# AnalogInputModule2_r1_1.net
KiCad netlist of a schematic drawn in EAGLE
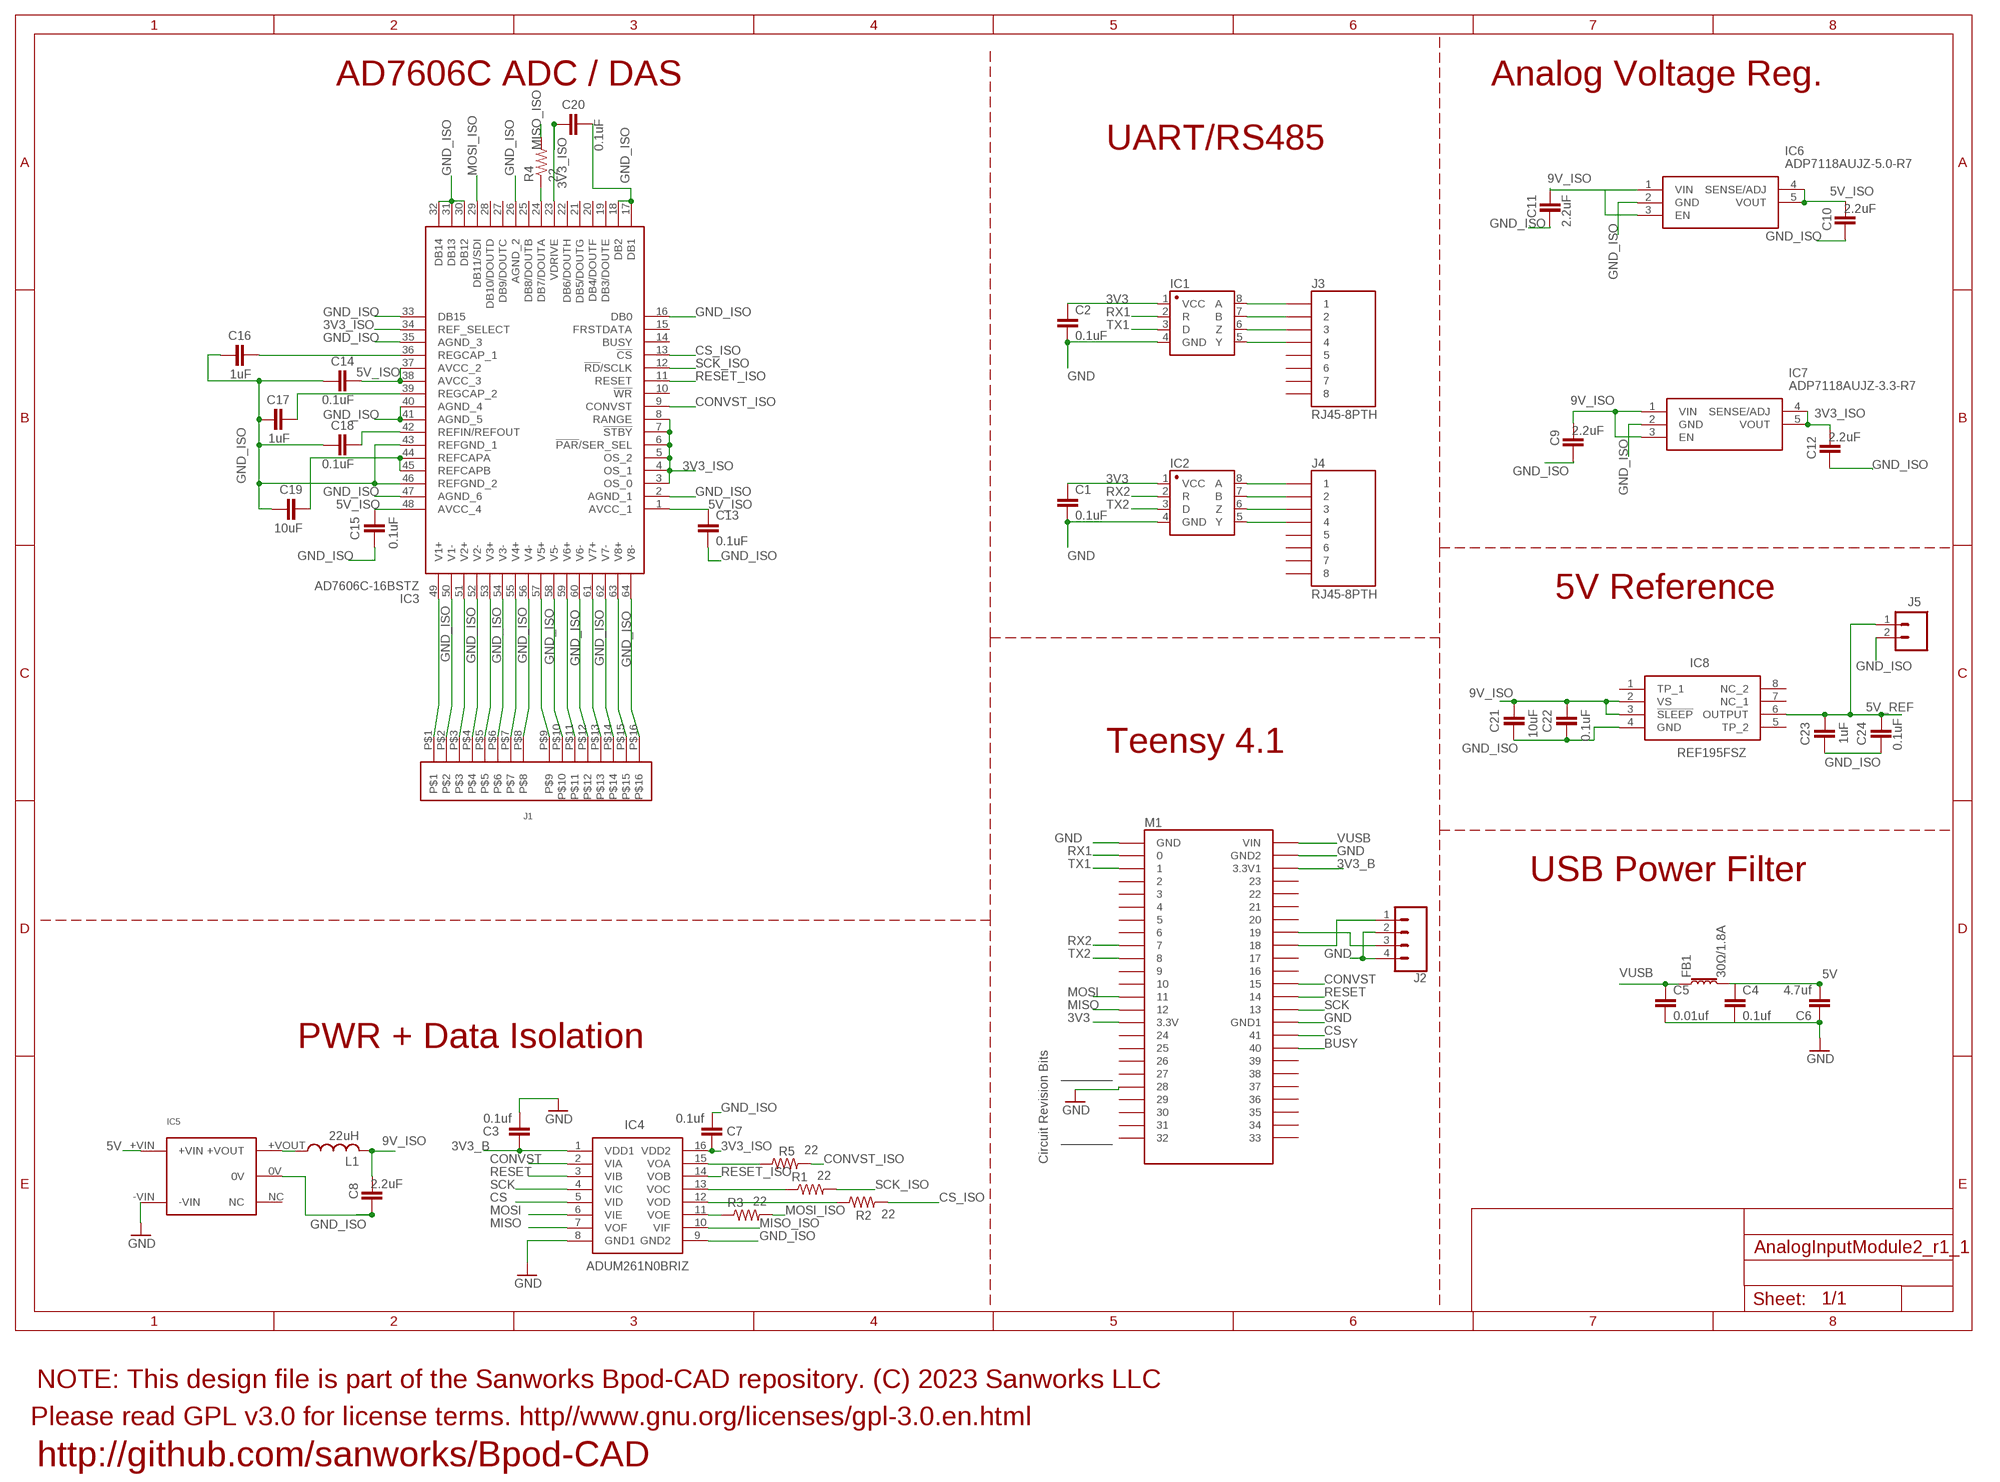
[diagram p0: schematic, sheet 1]

(export (version "E")
  (design (tool "Eeschema 10.0.6"))
  (components
    (comp (ref "C1")
      (value "0.1uF")
      (footprint "eagle-import:0805")
      (libsource (lib "eagle-import") (part "1.0UF-0805-25V-10%"))
    )
    (comp (ref "C2")
      (value "0.1uF")
      (footprint "eagle-import:0805")
      (libsource (lib "eagle-import") (part "1.0UF-0805-25V-10%"))
    )
    (comp (ref "C3")
      (value "0.1uf")
      (footprint "eagle-import:0805")
      (libsource (lib "eagle-import") (part "1.0UF-0805-25V-10%"))
    )
    (comp (ref "C4")
      (value "0.1uf")
      (footprint "eagle-import:0805")
      (libsource (lib "eagle-import") (part "10UF-0805-10V-10%"))
    )
    (comp (ref "C5")
      (value "0.01uf")
      (footprint "eagle-import:0805")
      (libsource (lib "eagle-import") (part "10UF-0805-10V-10%"))
    )
    (comp (ref "C6")
      (value "4.7uf")
      (footprint "eagle-import:1206@2")
      (libsource (lib "eagle-import") (part "CAP1206"))
    )
    (comp (ref "C7")
      (value "0.1uf")
      (footprint "eagle-import:0805")
      (libsource (lib "eagle-import") (part "1.0UF-0805-25V-10%"))
    )
    (comp (ref "C8")
      (value "2.2uF")
      (footprint "eagle-import:0805")
      (libsource (lib "eagle-import") (part "1.0UF-0805-25V-(+80/-20%)"))
    )
    (comp (ref "C9")
      (value "2.2uF")
      (footprint "eagle-import:0805")
      (libsource (lib "eagle-import") (part "1.0UF-0805-25V-(+80/-20%)"))
    )
    (comp (ref "C10")
      (value "2.2uF")
      (footprint "eagle-import:0805")
      (libsource (lib "eagle-import") (part "1.0UF-0805-25V-(+80/-20%)"))
    )
    (comp (ref "C11")
      (value "2.2uF")
      (footprint "eagle-import:0805")
      (libsource (lib "eagle-import") (part "1.0UF-0805-25V-(+80/-20%)"))
    )
    (comp (ref "C12")
      (value "2.2uF")
      (footprint "eagle-import:0805")
      (libsource (lib "eagle-import") (part "1.0UF-0805-25V-(+80/-20%)"))
    )
    (comp (ref "C13")
      (value "0.1uF")
      (footprint "eagle-import:0805")
      (libsource (lib "eagle-import") (part "1.0UF-0805-25V-10%"))
    )
    (comp (ref "C14")
      (value "0.1uF")
      (footprint "eagle-import:0805")
      (libsource (lib "eagle-import") (part "1.0UF-0805-25V-10%"))
    )
    (comp (ref "C15")
      (value "0.1uF")
      (footprint "eagle-import:0805")
      (libsource (lib "eagle-import") (part "1.0UF-0805-25V-10%"))
    )
    (comp (ref "C16")
      (value "1uF")
      (footprint "eagle-import:0805")
      (libsource (lib "eagle-import") (part "1.0UF-0805-25V-10%"))
    )
    (comp (ref "C17")
      (value "1uF")
      (footprint "eagle-import:0805")
      (libsource (lib "eagle-import") (part "1.0UF-0805-25V-10%"))
    )
    (comp (ref "C18")
      (value "0.1uF")
      (footprint "eagle-import:0805")
      (libsource (lib "eagle-import") (part "1.0UF-0805-25V-10%"))
    )
    (comp (ref "C19")
      (value "10uF")
      (footprint "eagle-import:0805")
      (libsource (lib "eagle-import") (part "1.0UF-0805-25V-10%"))
    )
    (comp (ref "C20")
      (value "0.1uF")
      (footprint "eagle-import:0805")
      (libsource (lib "eagle-import") (part "1.0UF-0805-25V-10%"))
    )
    (comp (ref "C21")
      (value "10uF")
      (footprint "eagle-import:0805")
      (libsource (lib "eagle-import") (part "1.0UF-0805-25V-10%"))
    )
    (comp (ref "C22")
      (value "0.1uF")
      (footprint "eagle-import:0805")
      (libsource (lib "eagle-import") (part "1.0UF-0805-25V-10%"))
    )
    (comp (ref "C23")
      (value "1uF")
      (footprint "eagle-import:0805")
      (libsource (lib "eagle-import") (part "1.0UF-0805-25V-10%"))
    )
    (comp (ref "C24")
      (value "0.1uF")
      (footprint "eagle-import:0805")
      (libsource (lib "eagle-import") (part "1.0UF-0805-25V-10%"))
    )
    (comp (ref "FB1")
      (value "30Ω/1.8A")
      (footprint "eagle-import:0603")
      (libsource (lib "eagle-import") (part "FERRITE_BEAD-0603"))
    )
    (comp (ref "IC1")
      (value "SN65HVD31DR")
      (footprint "eagle-import:SO08")
      (libsource (lib "eagle-import") (part "SN65HVD31DR"))
    )
    (comp (ref "IC2")
      (value "SN65HVD31DR")
      (footprint "eagle-import:SO08")
      (libsource (lib "eagle-import") (part "SN65HVD31DR"))
    )
    (comp (ref "IC3")
      (value "AD7606C-16BSTZ")
      (footprint "eagle-import:QFP50P1200X1200X160-64N")
      (fields (field (name "MOUSER_PART_NUMBER") "584-AD7606C-16BSTZ"))
      (libsource (lib "eagle-import") (part "AD7606C-16BSTZ"))
    )
    (comp (ref "IC4")
      (value "ADUM261N0BRIZ")
      (footprint "eagle-import:SOIC127P1030X264-16N")
      (fields (field (name "MOUSER_PART_NUMBER") "584-ADUM261N0BRIZ"))
      (libsource (lib "eagle-import") (part "ADUM261N0BRIZ"))
    )
    (comp (ref "IC5")
      (value "5V")
      (footprint "eagle-import:MTU1D0505MC")
      (libsource (lib "eagle-import") (part "MTU1D0505MC"))
    )
    (comp (ref "IC6")
      (value "ADP7118AUJZ-5.0-R7")
      (footprint "eagle-import:SOT95P280X100-5N")
      (fields (field (name "MOUSER_PART_NUMBER") "584-ADP7118AUJZ5.0R7"))
      (libsource (lib "eagle-import") (part "ADP7118AUJZ-5.0-R7"))
    )
    (comp (ref "IC7")
      (value "ADP7118AUJZ-3.3-R7")
      (footprint "eagle-import:SOT95P280X100-5N")
      (fields (field (name "MOUSER_PART_NUMBER") "584-ADP7118AUJZ3.3R7"))
      (libsource (lib "eagle-import") (part "ADP7118AUJZ-3.3-R7"))
    )
    (comp (ref "IC8")
      (value "REF195FSZ")
      (footprint "eagle-import:SOIC127P600X175-8N")
      (fields (field (name "MOUSER_PART_NUMBER") "584-REF195FSZ"))
      (libsource (lib "eagle-import") (part "REF195FSZ"))
    )
    (comp (ref "J1")
      (value "16POS_MOLEX_SOCKET")
      (footprint "eagle-import:16POS_MOLEX_SOCKET")
      (libsource (lib "eagle-import") (part "16POS_MOLEX_SOCKET"))
    )
    (comp (ref "J2")
      (value "CONN_04SCREW_LOCK")
      (footprint "eagle-import:SCREWTERMINAL-3.5MM-4_LOCK")
      (libsource (lib "eagle-import") (part "CONN_04SCREW_LOCK"))
    )
    (comp (ref "J3")
      (value "RJ45-8PTH")
      (footprint "eagle-import:RJ45-8")
      (libsource (lib "eagle-import") (part "RJ45-8PTH"))
    )
    (comp (ref "J4")
      (value "RJ45-8PTH")
      (footprint "eagle-import:RJ45-8")
      (libsource (lib "eagle-import") (part "RJ45-8PTH"))
    )
    (comp (ref "J5")
      (value "CONN_023.5MM_LOCK")
      (footprint "eagle-import:SCREWTERMINAL-3.5MM-2_LOCK")
      (libsource (lib "eagle-import") (part "CONN_023.5MM_LOCK"))
    )
    (comp (ref "L1")
      (value "22uH")
      (footprint "eagle-import:L3225M")
      (libsource (lib "eagle-import") (part "L-USL3225M"))
    )
    (comp (ref "M1")
      (value "TEENSY4.1_SIDESONLY")
      (footprint "eagle-import:TEENSY4.1_SIDESONLY")
      (libsource (lib "eagle-import") (part "TEENSY4.1_SIDESONLY"))
    )
    (comp (ref "R1")
      (value "22")
      (footprint "eagle-import:R0805")
      (libsource (lib "eagle-import") (part "R-US_R0805"))
    )
    (comp (ref "R2")
      (value "22")
      (footprint "eagle-import:R0805")
      (libsource (lib "eagle-import") (part "R-US_R0805"))
    )
    (comp (ref "R3")
      (value "22")
      (footprint "eagle-import:R0805")
      (libsource (lib "eagle-import") (part "R-US_R0805"))
    )
    (comp (ref "R4")
      (value "22")
      (footprint "eagle-import:R0805")
      (libsource (lib "eagle-import") (part "R-US_R0805"))
    )
    (comp (ref "R5")
      (value "22")
      (footprint "eagle-import:R0805")
      (libsource (lib "eagle-import") (part "R-US_R0805"))
    )
  )
  (nets
    (net (code "1") (name "/3V3") (class "Default")
      (node (ref "C1") (pin "1") (pinfunction "1_1") (pintype "passive"))
      (node (ref "C2") (pin "1") (pinfunction "1_1") (pintype "passive"))
      (node (ref "IC1") (pin "1") (pinfunction "VCC_1") (pintype "bidirectional"))
      (node (ref "IC2") (pin "1") (pinfunction "VCC_1") (pintype "bidirectional"))
      (node (ref "M1") (pin "3V3") (pinfunction "3.3V_3V3") (pintype "bidirectional"))
    )
    (net (code "2") (name "/3V3_B") (class "Default")
      (node (ref "C3") (pin "1") (pinfunction "1_1") (pintype "passive"))
      (node (ref "IC4") (pin "1") (pinfunction "VDD1_1") (pintype "bidirectional"))
      (node (ref "M1") (pin "3V3_LO") (pinfunction "3.3V1_3V3_LO") (pintype "bidirectional"))
    )
    (net (code "3") (name "/3V3_ISO") (class "Default")
      (node (ref "C12") (pin "2") (pinfunction "2_2") (pintype "passive"))
      (node (ref "C20") (pin "1") (pinfunction "1_1") (pintype "passive"))
      (node (ref "C7") (pin "1") (pinfunction "1_1") (pintype "passive"))
      (node (ref "IC3") (pin "23") (pinfunction "VDRIVE_23") (pintype "bidirectional"))
      (node (ref "IC3") (pin "3") (pinfunction "OS_0_3") (pintype "bidirectional"))
      (node (ref "IC3") (pin "34") (pinfunction "REF_SELECT_34") (pintype "bidirectional"))
      (node (ref "IC3") (pin "4") (pinfunction "OS_1_4") (pintype "bidirectional"))
      (node (ref "IC3") (pin "5") (pinfunction "OS_2_5") (pintype "bidirectional"))
      (node (ref "IC3") (pin "6") (pinfunction "~{PAR}/SER_SEL_6") (pintype "bidirectional"))
      (node (ref "IC3") (pin "7") (pinfunction "~{STBY}_7") (pintype "bidirectional"))
      (node (ref "IC3") (pin "8") (pinfunction "RANGE_8") (pintype "bidirectional"))
      (node (ref "IC4") (pin "16") (pinfunction "VDD2_16") (pintype "bidirectional"))
      (node (ref "IC7") (pin "4") (pinfunction "SENSE/ADJ_4") (pintype "bidirectional"))
      (node (ref "IC7") (pin "5") (pinfunction "VOUT_5") (pintype "bidirectional"))
    )
    (net (code "4") (name "/5V") (class "Default")
      (node (ref "C4") (pin "1") (pinfunction "1_1") (pintype "passive"))
      (node (ref "C6") (pin "2") (pinfunction "2_2") (pintype "passive"))
      (node (ref "FB1") (pin "2") (pinfunction "2_2") (pintype "passive"))
      (node (ref "IC5") (pin "+VIN") (pinfunction "+VIN_+VIN") (pintype "bidirectional"))
    )
    (net (code "5") (name "/5V_ISO") (class "Default")
      (node (ref "C10") (pin "2") (pinfunction "2_2") (pintype "passive"))
      (node (ref "C13") (pin "1") (pinfunction "1_1") (pintype "passive"))
      (node (ref "C14") (pin "2") (pinfunction "2_2") (pintype "passive"))
      (node (ref "C15") (pin "2") (pinfunction "2_2") (pintype "passive"))
      (node (ref "IC3") (pin "1") (pinfunction "AVCC_1_1") (pintype "bidirectional"))
      (node (ref "IC3") (pin "37") (pinfunction "AVCC_2_37") (pintype "bidirectional"))
      (node (ref "IC3") (pin "38") (pinfunction "AVCC_3_38") (pintype "bidirectional"))
      (node (ref "IC3") (pin "48") (pinfunction "AVCC_4_48") (pintype "bidirectional"))
      (node (ref "IC6") (pin "4") (pinfunction "SENSE/ADJ_4") (pintype "bidirectional"))
      (node (ref "IC6") (pin "5") (pinfunction "VOUT_5") (pintype "bidirectional"))
    )
    (net (code "6") (name "/5V_REF") (class "Default")
      (node (ref "C23") (pin "2") (pinfunction "2_2") (pintype "passive"))
      (node (ref "C24") (pin "2") (pinfunction "2_2") (pintype "passive"))
      (node (ref "IC8") (pin "6") (pinfunction "OUTPUT_6") (pintype "bidirectional"))
      (node (ref "J5") (pin "1") (pinfunction "1_1") (pintype "passive"))
    )
    (net (code "7") (name "/9V_ISO") (class "Default")
      (node (ref "C11") (pin "2") (pinfunction "2_2") (pintype "passive"))
      (node (ref "C21") (pin "2") (pinfunction "2_2") (pintype "passive"))
      (node (ref "C22") (pin "2") (pinfunction "2_2") (pintype "passive"))
      (node (ref "C8") (pin "2") (pinfunction "2_2") (pintype "passive"))
      (node (ref "C9") (pin "2") (pinfunction "2_2") (pintype "passive"))
      (node (ref "IC6") (pin "1") (pinfunction "VIN_1") (pintype "bidirectional"))
      (node (ref "IC6") (pin "3") (pinfunction "EN_3") (pintype "bidirectional"))
      (node (ref "IC7") (pin "1") (pinfunction "VIN_1") (pintype "bidirectional"))
      (node (ref "IC7") (pin "3") (pinfunction "EN_3") (pintype "bidirectional"))
      (node (ref "IC8") (pin "2") (pinfunction "VS_2") (pintype "bidirectional"))
      (node (ref "IC8") (pin "3") (pinfunction "~{SLEEP}_3") (pintype "bidirectional"))
      (node (ref "L1") (pin "2") (pinfunction "2_2") (pintype "passive"))
    )
    (net (code "8") (name "/BUSY") (class "Default")
      (node (ref "M1") (pin "40") (pinfunction "40_40") (pintype "bidirectional"))
    )
    (net (code "9") (name "/CONVST") (class "Default")
      (node (ref "IC4") (pin "2") (pinfunction "VIA_2") (pintype "bidirectional"))
      (node (ref "M1") (pin "15/A1") (pinfunction "15_15/A1") (pintype "bidirectional"))
    )
    (net (code "10") (name "/CONVST_ISO") (class "Default")
      (node (ref "IC3") (pin "9") (pinfunction "CONVST_9") (pintype "bidirectional"))
      (node (ref "R5") (pin "2") (pinfunction "2_2") (pintype "passive"))
    )
    (net (code "11") (name "/CS") (class "Default")
      (node (ref "IC4") (pin "5") (pinfunction "VID_5") (pintype "bidirectional"))
      (node (ref "M1") (pin "41") (pinfunction "41_41") (pintype "bidirectional"))
    )
    (net (code "12") (name "/CS_ISO") (class "Default")
      (node (ref "IC3") (pin "13") (pinfunction "~{CS}_13") (pintype "bidirectional"))
      (node (ref "R2") (pin "2") (pinfunction "2_2") (pintype "passive"))
    )
    (net (code "13") (name "/GND_ISO") (class "Default")
      (node (ref "C10") (pin "1") (pinfunction "1_1") (pintype "passive"))
      (node (ref "C11") (pin "1") (pinfunction "1_1") (pintype "passive"))
      (node (ref "C12") (pin "1") (pinfunction "1_1") (pintype "passive"))
      (node (ref "C13") (pin "2") (pinfunction "2_2") (pintype "passive"))
      (node (ref "C14") (pin "1") (pinfunction "1_1") (pintype "passive"))
      (node (ref "C15") (pin "1") (pinfunction "1_1") (pintype "passive"))
      (node (ref "C16") (pin "1") (pinfunction "1_1") (pintype "passive"))
      (node (ref "C17") (pin "1") (pinfunction "1_1") (pintype "passive"))
      (node (ref "C18") (pin "1") (pinfunction "1_1") (pintype "passive"))
      (node (ref "C19") (pin "1") (pinfunction "1_1") (pintype "passive"))
      (node (ref "C20") (pin "2") (pinfunction "2_2") (pintype "passive"))
      (node (ref "C21") (pin "1") (pinfunction "1_1") (pintype "passive"))
      (node (ref "C22") (pin "1") (pinfunction "1_1") (pintype "passive"))
      (node (ref "C23") (pin "1") (pinfunction "1_1") (pintype "passive"))
      (node (ref "C24") (pin "1") (pinfunction "1_1") (pintype "passive"))
      (node (ref "C7") (pin "2") (pinfunction "2_2") (pintype "passive"))
      (node (ref "C8") (pin "1") (pinfunction "1_1") (pintype "passive"))
      (node (ref "C9") (pin "1") (pinfunction "1_1") (pintype "passive"))
      (node (ref "IC3") (pin "16") (pinfunction "DB0_16") (pintype "bidirectional"))
      (node (ref "IC3") (pin "17") (pinfunction "DB1_17") (pintype "bidirectional"))
      (node (ref "IC3") (pin "18") (pinfunction "DB2_18") (pintype "bidirectional"))
      (node (ref "IC3") (pin "2") (pinfunction "AGND_1_2") (pintype "bidirectional"))
      (node (ref "IC3") (pin "26") (pinfunction "AGND_2_26") (pintype "bidirectional"))
      (node (ref "IC3") (pin "30") (pinfunction "DB12_30") (pintype "bidirectional"))
      (node (ref "IC3") (pin "31") (pinfunction "DB13_31") (pintype "bidirectional"))
      (node (ref "IC3") (pin "32") (pinfunction "DB14_32") (pintype "bidirectional"))
      (node (ref "IC3") (pin "33") (pinfunction "DB15_33") (pintype "bidirectional"))
      (node (ref "IC3") (pin "35") (pinfunction "AGND_3_35") (pintype "bidirectional"))
      (node (ref "IC3") (pin "40") (pinfunction "AGND_4_40") (pintype "bidirectional"))
      (node (ref "IC3") (pin "41") (pinfunction "AGND_5_41") (pintype "bidirectional"))
      (node (ref "IC3") (pin "43") (pinfunction "REFGND_1_43") (pintype "bidirectional"))
      (node (ref "IC3") (pin "46") (pinfunction "REFGND_2_46") (pintype "bidirectional"))
      (node (ref "IC3") (pin "47") (pinfunction "AGND_6_47") (pintype "bidirectional"))
      (node (ref "IC3") (pin "50") (pinfunction "V1-_50") (pintype "bidirectional"))
      (node (ref "IC3") (pin "52") (pinfunction "V2-_52") (pintype "bidirectional"))
      (node (ref "IC3") (pin "54") (pinfunction "V3-_54") (pintype "bidirectional"))
      (node (ref "IC3") (pin "56") (pinfunction "V4-_56") (pintype "bidirectional"))
      (node (ref "IC3") (pin "58") (pinfunction "V5-_58") (pintype "bidirectional"))
      (node (ref "IC3") (pin "60") (pinfunction "V6-_60") (pintype "bidirectional"))
      (node (ref "IC3") (pin "62") (pinfunction "V7-_62") (pintype "bidirectional"))
      (node (ref "IC3") (pin "64") (pinfunction "V8-_64") (pintype "bidirectional"))
      (node (ref "IC4") (pin "9") (pinfunction "GND2_9") (pintype "bidirectional"))
      (node (ref "IC5") (pin "0V") (pinfunction "0V_0V") (pintype "bidirectional"))
      (node (ref "IC6") (pin "2") (pinfunction "GND_2") (pintype "bidirectional"))
      (node (ref "IC7") (pin "2") (pinfunction "GND_2") (pintype "bidirectional"))
      (node (ref "IC8") (pin "4") (pinfunction "GND_4") (pintype "bidirectional"))
      (node (ref "J1") (pin "P$10") (pinfunction "P$10_P$10") (pintype "bidirectional"))
      (node (ref "J1") (pin "P$12") (pinfunction "P$12_P$12") (pintype "bidirectional"))
      (node (ref "J1") (pin "P$14") (pinfunction "P$14_P$14") (pintype "bidirectional"))
      (node (ref "J1") (pin "P$16") (pinfunction "P$16_P$16") (pintype "bidirectional"))
      (node (ref "J1") (pin "P$2") (pinfunction "P$2_P$2") (pintype "bidirectional"))
      (node (ref "J1") (pin "P$4") (pinfunction "P$4_P$4") (pintype "bidirectional"))
      (node (ref "J1") (pin "P$6") (pinfunction "P$6_P$6") (pintype "bidirectional"))
      (node (ref "J1") (pin "P$8") (pinfunction "P$8_P$8") (pintype "bidirectional"))
      (node (ref "J5") (pin "2") (pinfunction "2_2") (pintype "passive"))
    )
    (net (code "14") (name "/MISO") (class "Default")
      (node (ref "IC4") (pin "7") (pinfunction "VOF_7") (pintype "bidirectional"))
      (node (ref "M1") (pin "12/MISO") (pinfunction "12_12/MISO") (pintype "bidirectional"))
    )
    (net (code "15") (name "/MISO_ISO") (class "Default")
      (node (ref "IC4") (pin "10") (pinfunction "VIF_10") (pintype "bidirectional"))
      (node (ref "R4") (pin "2") (pinfunction "2_2") (pintype "passive"))
    )
    (net (code "16") (name "/MOSI") (class "Default")
      (node (ref "IC4") (pin "6") (pinfunction "VIE_6") (pintype "bidirectional"))
      (node (ref "M1") (pin "11/MOSI") (pinfunction "11_11/MOSI") (pintype "bidirectional"))
    )
    (net (code "17") (name "/MOSI_ISO") (class "Default")
      (node (ref "IC3") (pin "29") (pinfunction "DB11/SDI_29") (pintype "bidirectional"))
      (node (ref "R3") (pin "2") (pinfunction "2_2") (pintype "passive"))
    )
    (net (code "18") (name "/RESET") (class "Default")
      (node (ref "IC4") (pin "3") (pinfunction "VIB_3") (pintype "bidirectional"))
      (node (ref "M1") (pin "14/A0") (pinfunction "14_14/A0") (pintype "bidirectional"))
    )
    (net (code "19") (name "/RESET_ISO") (class "Default")
      (node (ref "IC3") (pin "11") (pinfunction "RESET_11") (pintype "bidirectional"))
      (node (ref "IC4") (pin "14") (pinfunction "VOB_14") (pintype "bidirectional"))
    )
    (net (code "20") (name "/RX1") (class "Default")
      (node (ref "IC1") (pin "2") (pinfunction "R_2") (pintype "bidirectional"))
      (node (ref "M1") (pin "0/RX") (pinfunction "0_0/RX") (pintype "bidirectional"))
    )
    (net (code "21") (name "/RX2") (class "Default")
      (node (ref "IC2") (pin "2") (pinfunction "R_2") (pintype "bidirectional"))
      (node (ref "M1") (pin "7") (pinfunction "7_7") (pintype "bidirectional"))
    )
    (net (code "22") (name "/SCK") (class "Default")
      (node (ref "IC4") (pin "4") (pinfunction "VIC_4") (pintype "bidirectional"))
      (node (ref "M1") (pin "13/SCK") (pinfunction "13_13/SCK") (pintype "bidirectional"))
    )
    (net (code "23") (name "/SCK_ISO") (class "Default")
      (node (ref "IC3") (pin "12") (pinfunction "~{RD}/SCLK_12") (pintype "bidirectional"))
      (node (ref "R1") (pin "2") (pinfunction "2_2") (pintype "passive"))
    )
    (net (code "24") (name "/TX1") (class "Default")
      (node (ref "IC1") (pin "3") (pinfunction "D_3") (pintype "bidirectional"))
      (node (ref "M1") (pin "1/TX") (pinfunction "1_1/TX") (pintype "bidirectional"))
    )
    (net (code "25") (name "/TX2") (class "Default")
      (node (ref "IC2") (pin "3") (pinfunction "D_3") (pintype "bidirectional"))
      (node (ref "M1") (pin "8") (pinfunction "8_8") (pintype "bidirectional"))
    )
    (net (code "26") (name "/VUSB") (class "Default")
      (node (ref "C5") (pin "1") (pinfunction "1_1") (pintype "passive"))
      (node (ref "FB1") (pin "1") (pinfunction "1_1") (pintype "passive"))
      (node (ref "M1") (pin "VIN") (pinfunction "VIN_VIN") (pintype "bidirectional"))
    )
    (net (code "27") (name "GND") (class "Default")
      (node (ref "C1") (pin "2") (pinfunction "2_2") (pintype "passive"))
      (node (ref "C2") (pin "2") (pinfunction "2_2") (pintype "passive"))
      (node (ref "C3") (pin "2") (pinfunction "2_2") (pintype "passive"))
      (node (ref "C4") (pin "2") (pinfunction "2_2") (pintype "passive"))
      (node (ref "C5") (pin "2") (pinfunction "2_2") (pintype "passive"))
      (node (ref "C6") (pin "1") (pinfunction "1_1") (pintype "passive"))
      (node (ref "IC1") (pin "4") (pinfunction "GND_4") (pintype "bidirectional"))
      (node (ref "IC2") (pin "4") (pinfunction "GND_4") (pintype "bidirectional"))
      (node (ref "IC4") (pin "8") (pinfunction "GND1_8") (pintype "bidirectional"))
      (node (ref "IC5") (pin "-VIN") (pinfunction "-VIN_-VIN") (pintype "bidirectional"))
      (node (ref "J2") (pin "2") (pinfunction "2_2") (pintype "passive"))
      (node (ref "J2") (pin "4") (pinfunction "4_4") (pintype "passive"))
      (node (ref "M1") (pin "28") (pinfunction "28_28") (pintype "bidirectional"))
      (node (ref "M1") (pin "AGND") (pinfunction "GND_AGND") (pintype "bidirectional"))
      (node (ref "M1") (pin "GND") (pinfunction "GND1_GND") (pintype "bidirectional"))
      (node (ref "M1") (pin "GND1") (pinfunction "GND2_GND1") (pintype "bidirectional"))
    )
    (net (code "28") (name "Net-(IC1-A)") (class "Default")
      (node (ref "IC1") (pin "8") (pinfunction "A_8") (pintype "bidirectional"))
      (node (ref "J3") (pin "1") (pinfunction "1_1") (pintype "bidirectional"))
    )
    (net (code "29") (name "Net-(IC1-B)") (class "Default")
      (node (ref "IC1") (pin "7") (pinfunction "B_7") (pintype "bidirectional"))
      (node (ref "J3") (pin "2") (pinfunction "2_2") (pintype "bidirectional"))
    )
    (net (code "30") (name "Net-(IC1-Y)") (class "Default")
      (node (ref "IC1") (pin "5") (pinfunction "Y_5") (pintype "bidirectional"))
      (node (ref "J3") (pin "4") (pinfunction "4_4") (pintype "bidirectional"))
    )
    (net (code "31") (name "Net-(IC1-Z)") (class "Default")
      (node (ref "IC1") (pin "6") (pinfunction "Z_6") (pintype "bidirectional"))
      (node (ref "J3") (pin "3") (pinfunction "3_3") (pintype "bidirectional"))
    )
    (net (code "32") (name "Net-(IC2-A)") (class "Default")
      (node (ref "IC2") (pin "8") (pinfunction "A_8") (pintype "bidirectional"))
      (node (ref "J4") (pin "1") (pinfunction "1_1") (pintype "bidirectional"))
    )
    (net (code "33") (name "Net-(IC2-B)") (class "Default")
      (node (ref "IC2") (pin "7") (pinfunction "B_7") (pintype "bidirectional"))
      (node (ref "J4") (pin "2") (pinfunction "2_2") (pintype "bidirectional"))
    )
    (net (code "34") (name "Net-(IC2-Y)") (class "Default")
      (node (ref "IC2") (pin "5") (pinfunction "Y_5") (pintype "bidirectional"))
      (node (ref "J4") (pin "4") (pinfunction "4_4") (pintype "bidirectional"))
    )
    (net (code "35") (name "Net-(IC2-Z)") (class "Default")
      (node (ref "IC2") (pin "6") (pinfunction "Z_6") (pintype "bidirectional"))
      (node (ref "J4") (pin "3") (pinfunction "3_3") (pintype "bidirectional"))
    )
    (net (code "36") (name "Net-(IC3-DB7{slash}DOUTA)") (class "Default")
      (node (ref "IC3") (pin "24") (pinfunction "DB7/DOUTA_24") (pintype "bidirectional"))
      (node (ref "R4") (pin "1") (pinfunction "1_1") (pintype "passive"))
    )
    (net (code "37") (name "Net-(IC3-REFCAPA)") (class "Default")
      (node (ref "C19") (pin "2") (pinfunction "2_2") (pintype "passive"))
      (node (ref "IC3") (pin "44") (pinfunction "REFCAPA_44") (pintype "bidirectional"))
      (node (ref "IC3") (pin "45") (pinfunction "REFCAPB_45") (pintype "bidirectional"))
    )
    (net (code "38") (name "Net-(IC3-REFIN{slash}REFOUT)") (class "Default")
      (node (ref "C18") (pin "2") (pinfunction "2_2") (pintype "passive"))
      (node (ref "IC3") (pin "42") (pinfunction "REFIN/REFOUT_42") (pintype "bidirectional"))
    )
    (net (code "39") (name "Net-(IC3-REGCAP_1)") (class "Default")
      (node (ref "C16") (pin "2") (pinfunction "2_2") (pintype "passive"))
      (node (ref "IC3") (pin "36") (pinfunction "REGCAP_1_36") (pintype "bidirectional"))
    )
    (net (code "40") (name "Net-(IC3-REGCAP_2)") (class "Default")
      (node (ref "C17") (pin "2") (pinfunction "2_2") (pintype "passive"))
      (node (ref "IC3") (pin "39") (pinfunction "REGCAP_2_39") (pintype "bidirectional"))
    )
    (net (code "41") (name "Net-(IC3-V1+)") (class "Default")
      (node (ref "IC3") (pin "49") (pinfunction "V1+_49") (pintype "bidirectional"))
      (node (ref "J1") (pin "P$1") (pinfunction "P$1_P$1") (pintype "bidirectional"))
    )
    (net (code "42") (name "Net-(IC3-V2+)") (class "Default")
      (node (ref "IC3") (pin "51") (pinfunction "V2+_51") (pintype "bidirectional"))
      (node (ref "J1") (pin "P$3") (pinfunction "P$3_P$3") (pintype "bidirectional"))
    )
    (net (code "43") (name "Net-(IC3-V3+)") (class "Default")
      (node (ref "IC3") (pin "53") (pinfunction "V3+_53") (pintype "bidirectional"))
      (node (ref "J1") (pin "P$5") (pinfunction "P$5_P$5") (pintype "bidirectional"))
    )
    (net (code "44") (name "Net-(IC3-V4+)") (class "Default")
      (node (ref "IC3") (pin "55") (pinfunction "V4+_55") (pintype "bidirectional"))
      (node (ref "J1") (pin "P$7") (pinfunction "P$7_P$7") (pintype "bidirectional"))
    )
    (net (code "45") (name "Net-(IC3-V5+)") (class "Default")
      (node (ref "IC3") (pin "57") (pinfunction "V5+_57") (pintype "bidirectional"))
      (node (ref "J1") (pin "P$9") (pinfunction "P$9_P$9") (pintype "bidirectional"))
    )
    (net (code "46") (name "Net-(IC3-V6+)") (class "Default")
      (node (ref "IC3") (pin "59") (pinfunction "V6+_59") (pintype "bidirectional"))
      (node (ref "J1") (pin "P$11") (pinfunction "P$11_P$11") (pintype "bidirectional"))
    )
    (net (code "47") (name "Net-(IC3-V7+)") (class "Default")
      (node (ref "IC3") (pin "61") (pinfunction "V7+_61") (pintype "bidirectional"))
      (node (ref "J1") (pin "P$13") (pinfunction "P$13_P$13") (pintype "bidirectional"))
    )
    (net (code "48") (name "Net-(IC3-V8+)") (class "Default")
      (node (ref "IC3") (pin "63") (pinfunction "V8+_63") (pintype "bidirectional"))
      (node (ref "J1") (pin "P$15") (pinfunction "P$15_P$15") (pintype "bidirectional"))
    )
    (net (code "49") (name "Net-(IC4-VOA)") (class "Default")
      (node (ref "IC4") (pin "15") (pinfunction "VOA_15") (pintype "bidirectional"))
      (node (ref "R5") (pin "1") (pinfunction "1_1") (pintype "passive"))
    )
    (net (code "50") (name "Net-(IC4-VOC)") (class "Default")
      (node (ref "IC4") (pin "13") (pinfunction "VOC_13") (pintype "bidirectional"))
      (node (ref "R1") (pin "1") (pinfunction "1_1") (pintype "passive"))
    )
    (net (code "51") (name "Net-(IC4-VOD)") (class "Default")
      (node (ref "IC4") (pin "12") (pinfunction "VOD_12") (pintype "bidirectional"))
      (node (ref "R2") (pin "1") (pinfunction "1_1") (pintype "passive"))
    )
    (net (code "52") (name "Net-(IC4-VOE)") (class "Default")
      (node (ref "IC4") (pin "11") (pinfunction "VOE_11") (pintype "bidirectional"))
      (node (ref "R3") (pin "1") (pinfunction "1_1") (pintype "passive"))
    )
    (net (code "53") (name "Net-(IC5-Pad+VOUT)") (class "Default")
      (node (ref "IC5") (pin "+VOUT") (pinfunction "+VOUT_+VOUT") (pintype "bidirectional"))
      (node (ref "L1") (pin "1") (pinfunction "1_1") (pintype "passive"))
    )
    (net (code "54") (name "Net-(M1-18)") (class "Default")
      (node (ref "J2") (pin "1") (pinfunction "1_1") (pintype "passive"))
      (node (ref "M1") (pin "18/A4/SDA") (pinfunction "18_18/A4/SDA") (pintype "bidirectional"))
    )
    (net (code "55") (name "Net-(M1-19)") (class "Default")
      (node (ref "J2") (pin "3") (pinfunction "3_3") (pintype "passive"))
      (node (ref "M1") (pin "19/A5/SCL") (pinfunction "19_19/A5/SCL") (pintype "bidirectional"))
    )
    (net (code "56") (name "unconnected-(IC3-BUSY-Pad14)") (class "Default")
      (node (ref "IC3") (pin "14") (pinfunction "BUSY_14") (pintype "bidirectional"))
    )
    (net (code "57") (name "unconnected-(IC3-DB3{slash}DOUTE-Pad19)") (class "Default")
      (node (ref "IC3") (pin "19") (pinfunction "DB3/DOUTE_19") (pintype "bidirectional"))
    )
    (net (code "58") (name "unconnected-(IC3-DB4{slash}DOUTF-Pad20)") (class "Default")
      (node (ref "IC3") (pin "20") (pinfunction "DB4/DOUTF_20") (pintype "bidirectional"))
    )
    (net (code "59") (name "unconnected-(IC3-DB5{slash}DOUTG-Pad21)") (class "Default")
      (node (ref "IC3") (pin "21") (pinfunction "DB5/DOUTG_21") (pintype "bidirectional"))
    )
    (net (code "60") (name "unconnected-(IC3-DB6{slash}DOUTH-Pad22)") (class "Default")
      (node (ref "IC3") (pin "22") (pinfunction "DB6/DOUTH_22") (pintype "bidirectional"))
    )
    (net (code "61") (name "unconnected-(IC3-DB8{slash}DOUTB-Pad25)") (class "Default")
      (node (ref "IC3") (pin "25") (pinfunction "DB8/DOUTB_25") (pintype "bidirectional"))
    )
    (net (code "62") (name "unconnected-(IC3-DB9{slash}DOUTC-Pad27)") (class "Default")
      (node (ref "IC3") (pin "27") (pinfunction "DB9/DOUTC_27") (pintype "bidirectional"))
    )
    (net (code "63") (name "unconnected-(IC3-DB10{slash}DOUTD-Pad28)") (class "Default")
      (node (ref "IC3") (pin "28") (pinfunction "DB10/DOUTD_28") (pintype "bidirectional"))
    )
    (net (code "64") (name "unconnected-(IC3-FRSTDATA-Pad15)") (class "Default")
      (node (ref "IC3") (pin "15") (pinfunction "FRSTDATA_15") (pintype "bidirectional"))
    )
    (net (code "65") (name "unconnected-(IC3-~{WR}-Pad10)") (class "Default")
      (node (ref "IC3") (pin "10") (pinfunction "~{WR}_10") (pintype "bidirectional"))
    )
    (net (code "66") (name "unconnected-(IC5-PadNC)") (class "Default")
      (node (ref "IC5") (pin "NC") (pinfunction "NC_NC") (pintype "bidirectional"))
    )
    (net (code "67") (name "unconnected-(IC8-NC_1-Pad7)") (class "Default")
      (node (ref "IC8") (pin "7") (pinfunction "NC_1_7") (pintype "bidirectional"))
    )
    (net (code "68") (name "unconnected-(IC8-NC_2-Pad8)") (class "Default")
      (node (ref "IC8") (pin "8") (pinfunction "NC_2_8") (pintype "bidirectional"))
    )
    (net (code "69") (name "unconnected-(IC8-TP_1-Pad1)") (class "Default")
      (node (ref "IC8") (pin "1") (pinfunction "TP_1_1") (pintype "bidirectional"))
    )
    (net (code "70") (name "unconnected-(IC8-TP_2-Pad5)") (class "Default")
      (node (ref "IC8") (pin "5") (pinfunction "TP_2_5") (pintype "bidirectional"))
    )
    (net (code "71") (name "unconnected-(J3-Pad5)") (class "Default")
      (node (ref "J3") (pin "5") (pinfunction "5_5") (pintype "bidirectional"))
    )
    (net (code "72") (name "unconnected-(J3-Pad6)") (class "Default")
      (node (ref "J3") (pin "6") (pinfunction "6_6") (pintype "bidirectional"))
    )
    (net (code "73") (name "unconnected-(J3-Pad7)") (class "Default")
      (node (ref "J3") (pin "7") (pinfunction "7_7") (pintype "bidirectional"))
    )
    (net (code "74") (name "unconnected-(J3-Pad8)") (class "Default")
      (node (ref "J3") (pin "8") (pinfunction "8_8") (pintype "bidirectional"))
    )
    (net (code "75") (name "unconnected-(J4-Pad5)") (class "Default")
      (node (ref "J4") (pin "5") (pinfunction "5_5") (pintype "bidirectional"))
    )
    (net (code "76") (name "unconnected-(J4-Pad6)") (class "Default")
      (node (ref "J4") (pin "6") (pinfunction "6_6") (pintype "bidirectional"))
    )
    (net (code "77") (name "unconnected-(J4-Pad7)") (class "Default")
      (node (ref "J4") (pin "7") (pinfunction "7_7") (pintype "bidirectional"))
    )
    (net (code "78") (name "unconnected-(J4-Pad8)") (class "Default")
      (node (ref "J4") (pin "8") (pinfunction "8_8") (pintype "bidirectional"))
    )
    (net (code "79") (name "unconnected-(M1-10-Pad10{slash}CS)") (class "Default")
      (node (ref "M1") (pin "10/CS") (pinfunction "10_10/CS") (pintype "bidirectional"))
    )
    (net (code "80") (name "unconnected-(M1-16-Pad16{slash}A2)") (class "Default")
      (node (ref "M1") (pin "16/A2") (pinfunction "16_16/A2") (pintype "bidirectional"))
    )
    (net (code "81") (name "unconnected-(M1-17-Pad17{slash}A3)") (class "Default")
      (node (ref "M1") (pin "17/A3") (pinfunction "17_17/A3") (pintype "bidirectional"))
    )
    (net (code "82") (name "unconnected-(M1-20-Pad20{slash}A6)") (class "Default")
      (node (ref "M1") (pin "20/A6") (pinfunction "20_20/A6") (pintype "bidirectional"))
    )
    (net (code "83") (name "unconnected-(M1-21-Pad21{slash}A7)") (class "Default")
      (node (ref "M1") (pin "21/A7") (pinfunction "21_21/A7") (pintype "bidirectional"))
    )
    (net (code "84") (name "unconnected-(M1-22-Pad22{slash}A8)") (class "Default")
      (node (ref "M1") (pin "22/A8") (pinfunction "22_22/A8") (pintype "bidirectional"))
    )
    (net (code "85") (name "unconnected-(M1-23-Pad23{slash}A9)") (class "Default")
      (node (ref "M1") (pin "23/A9") (pinfunction "23_23/A9") (pintype "bidirectional"))
    )
    (net (code "86") (name "unconnected-(M1-31-Pad31{slash}A12)") (class "Default")
      (node (ref "M1") (pin "31/A12") (pinfunction "31_31/A12") (pintype "bidirectional"))
    )
    (net (code "87") (name "unconnected-(M1-Pad2)") (class "Default")
      (node (ref "M1") (pin "2") (pinfunction "2_2") (pintype "bidirectional"))
    )
    (net (code "88") (name "unconnected-(M1-Pad3)") (class "Default")
      (node (ref "M1") (pin "3") (pinfunction "3_3") (pintype "bidirectional"))
    )
    (net (code "89") (name "unconnected-(M1-Pad4)") (class "Default")
      (node (ref "M1") (pin "4") (pinfunction "4_4") (pintype "bidirectional"))
    )
    (net (code "90") (name "unconnected-(M1-Pad5)") (class "Default")
      (node (ref "M1") (pin "5") (pinfunction "5_5") (pintype "bidirectional"))
    )
    (net (code "91") (name "unconnected-(M1-Pad6)") (class "Default")
      (node (ref "M1") (pin "6") (pinfunction "6_6") (pintype "bidirectional"))
    )
    (net (code "92") (name "unconnected-(M1-Pad9)") (class "Default")
      (node (ref "M1") (pin "9") (pinfunction "9_9") (pintype "bidirectional"))
    )
    (net (code "93") (name "unconnected-(M1-Pad24)") (class "Default")
      (node (ref "M1") (pin "24") (pinfunction "24_24") (pintype "bidirectional"))
    )
    (net (code "94") (name "unconnected-(M1-Pad25)") (class "Default")
      (node (ref "M1") (pin "25") (pinfunction "25_25") (pintype "bidirectional"))
    )
    (net (code "95") (name "unconnected-(M1-Pad26)") (class "Default")
      (node (ref "M1") (pin "26") (pinfunction "26_26") (pintype "bidirectional"))
    )
    (net (code "96") (name "unconnected-(M1-Pad27)") (class "Default")
      (node (ref "M1") (pin "27") (pinfunction "27_27") (pintype "bidirectional"))
    )
    (net (code "97") (name "unconnected-(M1-Pad29)") (class "Default")
      (node (ref "M1") (pin "29") (pinfunction "29_29") (pintype "bidirectional"))
    )
    (net (code "98") (name "unconnected-(M1-Pad30)") (class "Default")
      (node (ref "M1") (pin "30") (pinfunction "30_30") (pintype "bidirectional"))
    )
    (net (code "99") (name "unconnected-(M1-Pad32)") (class "Default")
      (node (ref "M1") (pin "32") (pinfunction "32_32") (pintype "bidirectional"))
    )
    (net (code "100") (name "unconnected-(M1-Pad33)") (class "Default")
      (node (ref "M1") (pin "33") (pinfunction "33_33") (pintype "bidirectional"))
    )
    (net (code "101") (name "unconnected-(M1-Pad34)") (class "Default")
      (node (ref "M1") (pin "34") (pinfunction "34_34") (pintype "bidirectional"))
    )
    (net (code "102") (name "unconnected-(M1-Pad35)") (class "Default")
      (node (ref "M1") (pin "35") (pinfunction "35_35") (pintype "bidirectional"))
    )
    (net (code "103") (name "unconnected-(M1-Pad36)") (class "Default")
      (node (ref "M1") (pin "36") (pinfunction "36_36") (pintype "bidirectional"))
    )
    (net (code "104") (name "unconnected-(M1-Pad37)") (class "Default")
      (node (ref "M1") (pin "37") (pinfunction "37_37") (pintype "bidirectional"))
    )
    (net (code "105") (name "unconnected-(M1-Pad38)") (class "Default")
      (node (ref "M1") (pin "38") (pinfunction "38_38") (pintype "bidirectional"))
    )
    (net (code "106") (name "unconnected-(M1-Pad39)") (class "Default")
      (node (ref "M1") (pin "39") (pinfunction "39_39") (pintype "bidirectional"))
    )
  )
)
